# 10bit-adc-and-dac-v2.net
KiCad netlist of a schematic drawn in EAGLE
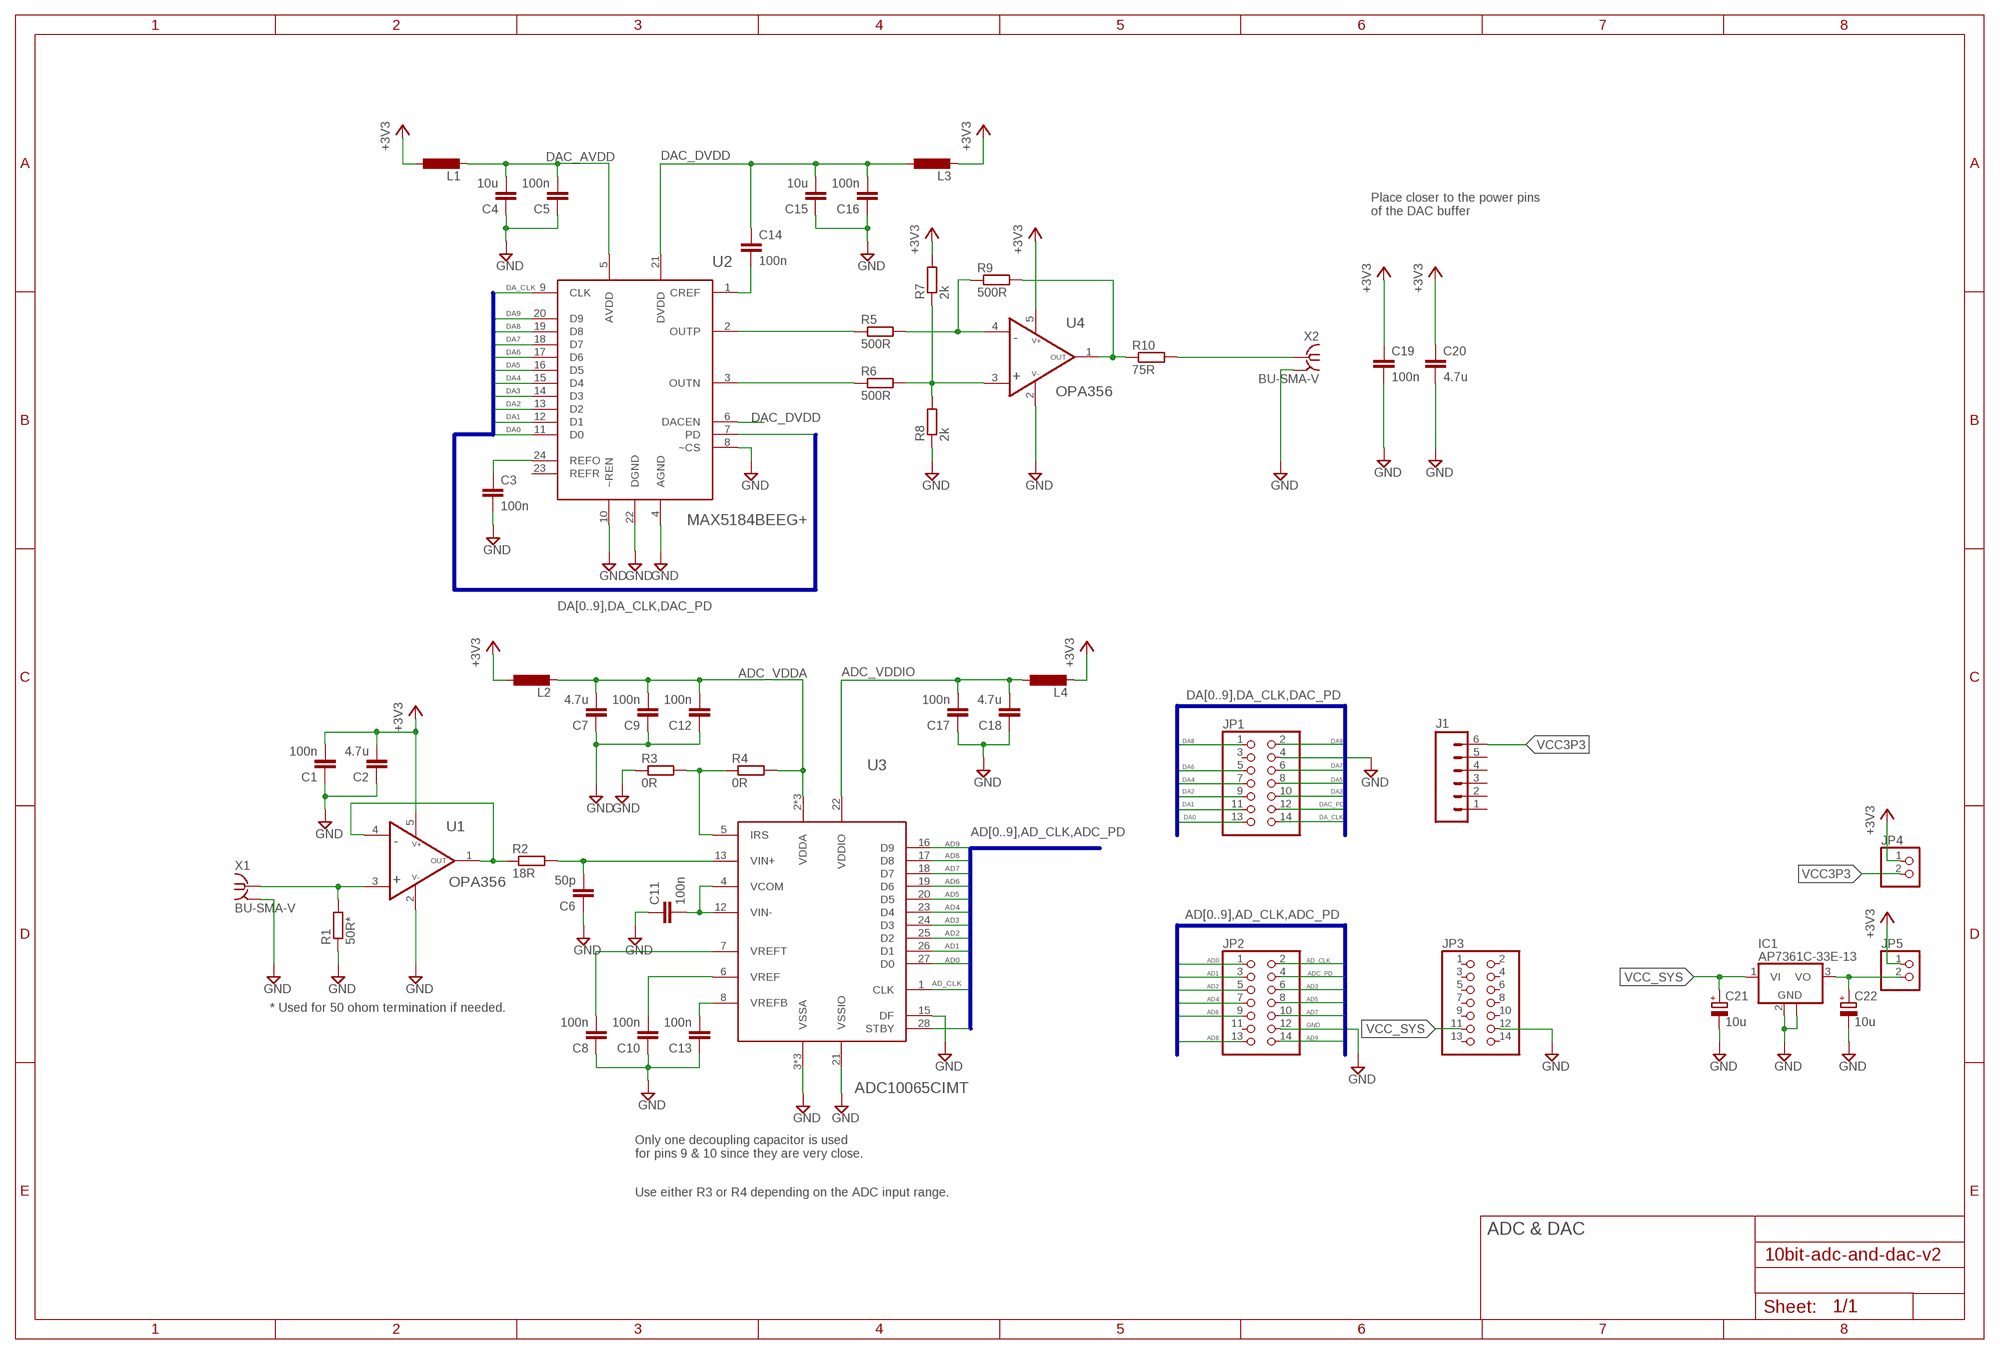
[diagram p0: schematic, sheet 1]

(export (version "E")
  (design (tool "Eeschema 10.0.6"))
  (components
    (comp (ref "C1")
      (value "100n")
      (footprint "eagle-import:C0805")
      (libsource (lib "eagle-import") (part "C-EUC0805"))
    )
    (comp (ref "C2")
      (value "4.7u")
      (footprint "eagle-import:C0805")
      (libsource (lib "eagle-import") (part "C-EUC0805"))
    )
    (comp (ref "C3")
      (value "100n")
      (footprint "eagle-import:C0805")
      (libsource (lib "eagle-import") (part "C-EUC0805"))
    )
    (comp (ref "C4")
      (value "10u")
      (footprint "eagle-import:C0805")
      (libsource (lib "eagle-import") (part "C-EUC0805"))
    )
    (comp (ref "C5")
      (value "100n")
      (footprint "eagle-import:C0805")
      (libsource (lib "eagle-import") (part "C-EUC0805"))
    )
    (comp (ref "C6")
      (value "50p")
      (footprint "eagle-import:C0805")
      (libsource (lib "eagle-import") (part "C-EUC0805"))
    )
    (comp (ref "C7")
      (value "4.7u")
      (footprint "eagle-import:C0805")
      (libsource (lib "eagle-import") (part "C-EUC0805"))
    )
    (comp (ref "C8")
      (value "100n")
      (footprint "eagle-import:C0805")
      (libsource (lib "eagle-import") (part "C-EUC0805"))
    )
    (comp (ref "C9")
      (value "100n")
      (footprint "eagle-import:C0805")
      (libsource (lib "eagle-import") (part "C-EUC0805"))
    )
    (comp (ref "C10")
      (value "100n")
      (footprint "eagle-import:C0805")
      (libsource (lib "eagle-import") (part "C-EUC0805"))
    )
    (comp (ref "C11")
      (value "100n")
      (footprint "eagle-import:C0805")
      (libsource (lib "eagle-import") (part "C-EUC0805"))
    )
    (comp (ref "C12")
      (value "100n")
      (footprint "eagle-import:C0805")
      (libsource (lib "eagle-import") (part "C-EUC0805"))
    )
    (comp (ref "C13")
      (value "100n")
      (footprint "eagle-import:C0805")
      (libsource (lib "eagle-import") (part "C-EUC0805"))
    )
    (comp (ref "C14")
      (value "100n")
      (footprint "eagle-import:C0805")
      (libsource (lib "eagle-import") (part "C-EUC0805"))
    )
    (comp (ref "C15")
      (value "10u")
      (footprint "eagle-import:C0805")
      (libsource (lib "eagle-import") (part "C-EUC0805"))
    )
    (comp (ref "C16")
      (value "100n")
      (footprint "eagle-import:C0805")
      (libsource (lib "eagle-import") (part "C-EUC0805"))
    )
    (comp (ref "C17")
      (value "100n")
      (footprint "eagle-import:C0805")
      (libsource (lib "eagle-import") (part "C-EUC0805"))
    )
    (comp (ref "C18")
      (value "4.7u")
      (footprint "eagle-import:C0805")
      (libsource (lib "eagle-import") (part "C-EUC0805"))
    )
    (comp (ref "C19")
      (value "100n")
      (footprint "eagle-import:C0805")
      (libsource (lib "eagle-import") (part "C-EUC0805"))
    )
    (comp (ref "C20")
      (value "4.7u")
      (footprint "eagle-import:C0805")
      (libsource (lib "eagle-import") (part "C-EUC0805"))
    )
    (comp (ref "C21")
      (value "10u")
      (footprint "eagle-import:CT3528")
      (libsource (lib "eagle-import") (part "CPOL-EUCT3528"))
    )
    (comp (ref "C22")
      (value "10u")
      (footprint "eagle-import:CT3528")
      (libsource (lib "eagle-import") (part "CPOL-EUCT3528"))
    )
    (comp (ref "IC1")
      (value "AP7361C-33E-13")
      (footprint "eagle-import:SOT223")
      (fields (field (name "MF") "Diodes Incorporated"))
      (libsource (lib "eagle-import") (part "UA78MDCY33"))
    )
    (comp (ref "J1")
      (value "M06SILK_FEMALE_PTH")
      (footprint "eagle-import:1X06")
      (libsource (lib "eagle-import") (part "M06SILK_FEMALE_PTH"))
    )
    (comp (ref "JP1")
      (value "PINHD-2X7")
      (footprint "eagle-import:2X07")
      (libsource (lib "eagle-import") (part "PINHD-2X7"))
    )
    (comp (ref "JP2")
      (value "PINHD-2X7")
      (footprint "eagle-import:2X07")
      (libsource (lib "eagle-import") (part "PINHD-2X7"))
    )
    (comp (ref "JP3")
      (value "PINHD-2X7")
      (footprint "eagle-import:2X07")
      (libsource (lib "eagle-import") (part "PINHD-2X7"))
    )
    (comp (ref "JP4")
      (value "PINHD-1X2")
      (footprint "eagle-import:1X02")
      (libsource (lib "eagle-import") (part "PINHD-1X2"))
    )
    (comp (ref "JP5")
      (value "PINHD-1X2")
      (footprint "eagle-import:1X02")
      (libsource (lib "eagle-import") (part "PINHD-1X2"))
    )
    (comp (ref "L1")
      (value "L-EUL2012C")
      (footprint "eagle-import:L2012C")
      (fields (field (name "MPN") "CIM21J252NE"))
      (libsource (lib "eagle-import") (part "L-EUL2012C"))
    )
    (comp (ref "L2")
      (value "L-EUL2012C")
      (footprint "eagle-import:L2012C")
      (fields (field (name "MPN") "CIM21J252NE"))
      (libsource (lib "eagle-import") (part "L-EUL2012C"))
    )
    (comp (ref "L3")
      (value "L-EUL2012C")
      (footprint "eagle-import:L2012C")
      (fields (field (name "MPN") "CIM21J252NE"))
      (libsource (lib "eagle-import") (part "L-EUL2012C"))
    )
    (comp (ref "L4")
      (value "L-EUL2012C")
      (footprint "eagle-import:L2012C")
      (fields (field (name "MPN") "CIM21J252NE"))
      (libsource (lib "eagle-import") (part "L-EUL2012C"))
    )
    (comp (ref "R1")
      (value "50R*")
      (footprint "eagle-import:R0805")
      (libsource (lib "eagle-import") (part "R-EU_R0805"))
    )
    (comp (ref "R2")
      (value "18R")
      (footprint "eagle-import:R0805")
      (libsource (lib "eagle-import") (part "R-EU_R0805"))
    )
    (comp (ref "R3")
      (value "0R")
      (footprint "eagle-import:R0805")
      (libsource (lib "eagle-import") (part "R-EU_R0805"))
    )
    (comp (ref "R4")
      (value "0R")
      (footprint "eagle-import:R0805")
      (libsource (lib "eagle-import") (part "R-EU_R0805"))
    )
    (comp (ref "R5")
      (value "500R")
      (footprint "eagle-import:R0805")
      (libsource (lib "eagle-import") (part "R-EU_R0805"))
    )
    (comp (ref "R6")
      (value "500R")
      (footprint "eagle-import:R0805")
      (libsource (lib "eagle-import") (part "R-EU_R0805"))
    )
    (comp (ref "R7")
      (value "2k")
      (footprint "eagle-import:R0805")
      (libsource (lib "eagle-import") (part "R-EU_R0805"))
    )
    (comp (ref "R8")
      (value "2k")
      (footprint "eagle-import:R0805")
      (libsource (lib "eagle-import") (part "R-EU_R0805"))
    )
    (comp (ref "R9")
      (value "500R")
      (footprint "eagle-import:R0805")
      (libsource (lib "eagle-import") (part "R-EU_R0805"))
    )
    (comp (ref "R10")
      (value "75R")
      (footprint "eagle-import:R0805")
      (libsource (lib "eagle-import") (part "R-EU_R0805"))
    )
    (comp (ref "U1")
      (value "OPA356")
      (footprint "eagle-import:SOT23-5L")
      (fields (field (name "MF") "TI") (field (name "MPN") "OPA356AIDBVR"))
      (libsource (lib "eagle-import") (part "OPA356"))
    )
    (comp (ref "U2")
      (value "MAX5184BEEG+")
      (footprint "eagle-import:SOP63P600X175-24N")
      (fields (field (name "MF") "MAXIM"))
      (libsource (lib "eagle-import") (part "MAX5184BEEG+"))
    )
    (comp (ref "U3")
      (value "ADC10065CIMT")
      (footprint "eagle-import:TSSOP28")
      (fields (field (name "MF") "TI") (field (name "MPN") "ADC10065CIMTX/NOPB"))
      (libsource (lib "eagle-import") (part "ADC10065CIMT"))
    )
    (comp (ref "U4")
      (value "OPA356")
      (footprint "eagle-import:SOT23-5L")
      (fields (field (name "MF") "TI") (field (name "MPN") "OPA356AIDBVR"))
      (libsource (lib "eagle-import") (part "OPA356"))
    )
    (comp (ref "X1")
      (value "BU-SMA-V")
      (footprint "eagle-import:BU-SMA-V")
      (fields (field (name "MF") "TE Connectivity") (field (name "MPN") "5-1814832-1"))
      (libsource (lib "eagle-import") (part "BU-SMA-V"))
    )
    (comp (ref "X2")
      (value "BU-SMA-V")
      (footprint "eagle-import:BU-SMA-V")
      (fields (field (name "MF") "TE Connectivity") (field (name "MPN") "5-1814832-1"))
      (libsource (lib "eagle-import") (part "BU-SMA-V"))
    )
  )
  (nets
    (net (code "1") (name "+3V3") (class "Default")
      (node (ref "C1") (pin "2") (pinfunction "2_2") (pintype "passive"))
      (node (ref "C19") (pin "1") (pinfunction "1_1") (pintype "passive"))
      (node (ref "C2") (pin "2") (pinfunction "2_2") (pintype "passive"))
      (node (ref "C20") (pin "1") (pinfunction "1_1") (pintype "passive"))
      (node (ref "JP4") (pin "1") (pinfunction "1_1") (pintype "passive"))
      (node (ref "JP5") (pin "1") (pinfunction "1_1") (pintype "passive"))
      (node (ref "L1") (pin "1") (pinfunction "1_1") (pintype "passive"))
      (node (ref "L2") (pin "1") (pinfunction "1_1") (pintype "passive"))
      (node (ref "L3") (pin "2") (pinfunction "2_2") (pintype "passive"))
      (node (ref "L4") (pin "2") (pinfunction "2_2") (pintype "passive"))
      (node (ref "R7") (pin "2") (pinfunction "2_2") (pintype "passive"))
      (node (ref "U1") (pin "5") (pinfunction "V+_5") (pintype "power_in"))
      (node (ref "U4") (pin "5") (pinfunction "V+_5") (pintype "power_in"))
    )
    (net (code "2") (name "/AD0") (class "Default")
      (node (ref "JP2") (pin "1") (pinfunction "1_1") (pintype "passive"))
      (node (ref "U3") (pin "27") (pinfunction "D0_27") (pintype "bidirectional"))
    )
    (net (code "3") (name "/AD1") (class "Default")
      (node (ref "JP2") (pin "3") (pinfunction "3_3") (pintype "passive"))
      (node (ref "U3") (pin "26") (pinfunction "D1_26") (pintype "bidirectional"))
    )
    (net (code "4") (name "/AD2") (class "Default")
      (node (ref "JP2") (pin "5") (pinfunction "5_5") (pintype "passive"))
      (node (ref "U3") (pin "25") (pinfunction "D2_25") (pintype "bidirectional"))
    )
    (net (code "5") (name "/AD3") (class "Default")
      (node (ref "JP2") (pin "6") (pinfunction "6_6") (pintype "passive"))
      (node (ref "U3") (pin "24") (pinfunction "D3_24") (pintype "bidirectional"))
    )
    (net (code "6") (name "/AD4") (class "Default")
      (node (ref "JP2") (pin "7") (pinfunction "7_7") (pintype "passive"))
      (node (ref "U3") (pin "23") (pinfunction "D4_23") (pintype "bidirectional"))
    )
    (net (code "7") (name "/AD5") (class "Default")
      (node (ref "JP2") (pin "8") (pinfunction "8_8") (pintype "passive"))
      (node (ref "U3") (pin "20") (pinfunction "D5_20") (pintype "bidirectional"))
    )
    (net (code "8") (name "/AD6") (class "Default")
      (node (ref "JP2") (pin "9") (pinfunction "9_9") (pintype "passive"))
      (node (ref "U3") (pin "19") (pinfunction "D6_19") (pintype "bidirectional"))
    )
    (net (code "9") (name "/AD7") (class "Default")
      (node (ref "JP2") (pin "10") (pinfunction "10_10") (pintype "passive"))
      (node (ref "U3") (pin "18") (pinfunction "D7_18") (pintype "bidirectional"))
    )
    (net (code "10") (name "/AD8") (class "Default")
      (node (ref "JP2") (pin "13") (pinfunction "13_13") (pintype "passive"))
      (node (ref "U3") (pin "17") (pinfunction "D8_17") (pintype "bidirectional"))
    )
    (net (code "11") (name "/AD9") (class "Default")
      (node (ref "JP2") (pin "14") (pinfunction "14_14") (pintype "passive"))
      (node (ref "U3") (pin "16") (pinfunction "D9_16") (pintype "bidirectional"))
    )
    (net (code "12") (name "/ADC_PD") (class "Default")
      (node (ref "JP2") (pin "4") (pinfunction "4_4") (pintype "passive"))
      (node (ref "U3") (pin "28") (pinfunction "STBY_28") (pintype "bidirectional"))
    )
    (net (code "13") (name "/ADC_VDDA") (class "Default")
      (node (ref "C12") (pin "2") (pinfunction "2_2") (pintype "passive"))
      (node (ref "C7") (pin "2") (pinfunction "2_2") (pintype "passive"))
      (node (ref "C9") (pin "2") (pinfunction "2_2") (pintype "passive"))
      (node (ref "L2") (pin "2") (pinfunction "2_2") (pintype "passive"))
      (node (ref "R4") (pin "2") (pinfunction "2_2") (pintype "passive"))
      (node (ref "U3") (pin "10") (pinfunction "VDDA_10") (pintype "bidirectional"))
      (node (ref "U3") (pin "2") (pinfunction "VDDA_2") (pintype "bidirectional"))
      (node (ref "U3") (pin "9") (pinfunction "VDDA_9") (pintype "bidirectional"))
    )
    (net (code "14") (name "/ADC_VDDIO") (class "Default")
      (node (ref "C17") (pin "2") (pinfunction "2_2") (pintype "passive"))
      (node (ref "C18") (pin "2") (pinfunction "2_2") (pintype "passive"))
      (node (ref "L4") (pin "1") (pinfunction "1_1") (pintype "passive"))
      (node (ref "U3") (pin "22") (pinfunction "VDDIO_22") (pintype "bidirectional"))
    )
    (net (code "15") (name "/AD_CLK") (class "Default")
      (node (ref "JP2") (pin "2") (pinfunction "2_2") (pintype "passive"))
      (node (ref "U3") (pin "1") (pinfunction "CLK_1") (pintype "bidirectional"))
    )
    (net (code "16") (name "/DA0") (class "Default")
      (node (ref "JP1") (pin "13") (pinfunction "13_13") (pintype "passive"))
      (node (ref "U2") (pin "11") (pinfunction "D0_11") (pintype "bidirectional"))
    )
    (net (code "17") (name "/DA1") (class "Default")
      (node (ref "JP1") (pin "11") (pinfunction "11_11") (pintype "passive"))
      (node (ref "U2") (pin "12") (pinfunction "D1_12") (pintype "bidirectional"))
    )
    (net (code "18") (name "/DA2") (class "Default")
      (node (ref "JP1") (pin "9") (pinfunction "9_9") (pintype "passive"))
      (node (ref "U2") (pin "13") (pinfunction "D2_13") (pintype "bidirectional"))
    )
    (net (code "19") (name "/DA3") (class "Default")
      (node (ref "JP1") (pin "10") (pinfunction "10_10") (pintype "passive"))
      (node (ref "U2") (pin "14") (pinfunction "D3_14") (pintype "bidirectional"))
    )
    (net (code "20") (name "/DA4") (class "Default")
      (node (ref "JP1") (pin "7") (pinfunction "7_7") (pintype "passive"))
      (node (ref "U2") (pin "15") (pinfunction "D4_15") (pintype "bidirectional"))
    )
    (net (code "21") (name "/DA5") (class "Default")
      (node (ref "JP1") (pin "8") (pinfunction "8_8") (pintype "passive"))
      (node (ref "U2") (pin "16") (pinfunction "D5_16") (pintype "bidirectional"))
    )
    (net (code "22") (name "/DA6") (class "Default")
      (node (ref "JP1") (pin "5") (pinfunction "5_5") (pintype "passive"))
      (node (ref "U2") (pin "17") (pinfunction "D6_17") (pintype "bidirectional"))
    )
    (net (code "23") (name "/DA7") (class "Default")
      (node (ref "JP1") (pin "6") (pinfunction "6_6") (pintype "passive"))
      (node (ref "U2") (pin "18") (pinfunction "D7_18") (pintype "bidirectional"))
    )
    (net (code "24") (name "/DA8") (class "Default")
      (node (ref "JP1") (pin "1") (pinfunction "1_1") (pintype "passive"))
      (node (ref "U2") (pin "19") (pinfunction "D8_19") (pintype "bidirectional"))
    )
    (net (code "25") (name "/DA9") (class "Default")
      (node (ref "JP1") (pin "2") (pinfunction "2_2") (pintype "passive"))
      (node (ref "U2") (pin "20") (pinfunction "D9_20") (pintype "bidirectional"))
    )
    (net (code "26") (name "/DAC_AVDD") (class "Default")
      (node (ref "C4") (pin "2") (pinfunction "2_2") (pintype "passive"))
      (node (ref "C5") (pin "2") (pinfunction "2_2") (pintype "passive"))
      (node (ref "L1") (pin "2") (pinfunction "2_2") (pintype "passive"))
      (node (ref "U2") (pin "5") (pinfunction "AVDD_5") (pintype "bidirectional"))
    )
    (net (code "27") (name "/DAC_DVDD") (class "Default")
      (node (ref "C14") (pin "1") (pinfunction "1_1") (pintype "passive"))
      (node (ref "C15") (pin "2") (pinfunction "2_2") (pintype "passive"))
      (node (ref "C16") (pin "2") (pinfunction "2_2") (pintype "passive"))
      (node (ref "L3") (pin "1") (pinfunction "1_1") (pintype "passive"))
      (node (ref "U2") (pin "21") (pinfunction "DVDD_21") (pintype "bidirectional"))
      (node (ref "U2") (pin "6") (pinfunction "DACEN_6") (pintype "bidirectional"))
    )
    (net (code "28") (name "/DAC_PD") (class "Default")
      (node (ref "JP1") (pin "12") (pinfunction "12_12") (pintype "passive"))
      (node (ref "U2") (pin "7") (pinfunction "PD_7") (pintype "bidirectional"))
    )
    (net (code "29") (name "/DA_CLK") (class "Default")
      (node (ref "JP1") (pin "14") (pinfunction "14_14") (pintype "passive"))
      (node (ref "U2") (pin "9") (pinfunction "CLK_9") (pintype "bidirectional"))
    )
    (net (code "32") (name "GND") (class "Default")
      (node (ref "C1") (pin "1") (pinfunction "1_1") (pintype "passive"))
      (node (ref "C10") (pin "1") (pinfunction "1_1") (pintype "passive"))
      (node (ref "C11") (pin "1") (pinfunction "1_1") (pintype "passive"))
      (node (ref "C12") (pin "1") (pinfunction "1_1") (pintype "passive"))
      (node (ref "C13") (pin "1") (pinfunction "1_1") (pintype "passive"))
      (node (ref "C15") (pin "1") (pinfunction "1_1") (pintype "passive"))
      (node (ref "C16") (pin "1") (pinfunction "1_1") (pintype "passive"))
      (node (ref "C17") (pin "1") (pinfunction "1_1") (pintype "passive"))
      (node (ref "C18") (pin "1") (pinfunction "1_1") (pintype "passive"))
      (node (ref "C19") (pin "2") (pinfunction "2_2") (pintype "passive"))
      (node (ref "C2") (pin "1") (pinfunction "1_1") (pintype "passive"))
      (node (ref "C20") (pin "2") (pinfunction "2_2") (pintype "passive"))
      (node (ref "C21") (pin "-") (pinfunction "-_-") (pintype "passive"))
      (node (ref "C22") (pin "-") (pinfunction "-_-") (pintype "passive"))
      (node (ref "C3") (pin "2") (pinfunction "2_2") (pintype "passive"))
      (node (ref "C4") (pin "1") (pinfunction "1_1") (pintype "passive"))
      (node (ref "C5") (pin "1") (pinfunction "1_1") (pintype "passive"))
      (node (ref "C6") (pin "1") (pinfunction "1_1") (pintype "passive"))
      (node (ref "C7") (pin "1") (pinfunction "1_1") (pintype "passive"))
      (node (ref "C8") (pin "1") (pinfunction "1_1") (pintype "passive"))
      (node (ref "C9") (pin "1") (pinfunction "1_1") (pintype "passive"))
      (node (ref "IC1") (pin "2") (pinfunction "GND_2") (pintype "passive"))
      (node (ref "IC1") (pin "4") (pinfunction "GND_4") (pintype "passive"))
      (node (ref "JP1") (pin "4") (pinfunction "4_4") (pintype "passive"))
      (node (ref "JP2") (pin "12") (pinfunction "12_12") (pintype "passive"))
      (node (ref "JP3") (pin "12") (pinfunction "12_12") (pintype "passive"))
      (node (ref "R1") (pin "1") (pinfunction "1_1") (pintype "passive"))
      (node (ref "R3") (pin "1") (pinfunction "1_1") (pintype "passive"))
      (node (ref "R8") (pin "1") (pinfunction "1_1") (pintype "passive"))
      (node (ref "U1") (pin "2") (pinfunction "V-_2") (pintype "power_in"))
      (node (ref "U2") (pin "10") (pinfunction "~{REN}_10") (pintype "bidirectional"))
      (node (ref "U2") (pin "22") (pinfunction "DGND_22") (pintype "bidirectional"))
      (node (ref "U2") (pin "4") (pinfunction "AGND_4") (pintype "bidirectional"))
      (node (ref "U2") (pin "8") (pinfunction "~{CS}_8") (pintype "bidirectional"))
      (node (ref "U3") (pin "11") (pinfunction "VSSA_11") (pintype "bidirectional"))
      (node (ref "U3") (pin "14") (pinfunction "VSSA_14") (pintype "bidirectional"))
      (node (ref "U3") (pin "15") (pinfunction "DF_15") (pintype "bidirectional"))
      (node (ref "U3") (pin "21") (pinfunction "VSSIO_21") (pintype "bidirectional"))
      (node (ref "U3") (pin "3") (pinfunction "VSSA_3") (pintype "bidirectional"))
      (node (ref "U4") (pin "2") (pinfunction "V-_2") (pintype "power_in"))
      (node (ref "X1") (pin "2") (pinfunction "2_2") (pintype "passive"))
      (node (ref "X1") (pin "3") (pinfunction "2_3") (pintype "passive"))
      (node (ref "X1") (pin "4") (pinfunction "2_4") (pintype "passive"))
      (node (ref "X1") (pin "5") (pinfunction "2_5") (pintype "passive"))
      (node (ref "X2") (pin "2") (pinfunction "2_2") (pintype "passive"))
      (node (ref "X2") (pin "3") (pinfunction "2_3") (pintype "passive"))
      (node (ref "X2") (pin "4") (pinfunction "2_4") (pintype "passive"))
      (node (ref "X2") (pin "5") (pinfunction "2_5") (pintype "passive"))
    )
    (net (code "33") (name "Net-(IC1-VO)") (class "Default")
      (node (ref "C22") (pin "+") (pinfunction "+_+") (pintype "passive"))
      (node (ref "IC1") (pin "3") (pinfunction "VO_3") (pintype "passive"))
      (node (ref "JP5") (pin "2") (pinfunction "2_2") (pintype "passive"))
    )
    (net (code "34") (name "Net-(R10-Pad2)") (class "Default")
      (node (ref "R10") (pin "2") (pinfunction "2_2") (pintype "passive"))
      (node (ref "X2") (pin "1") (pinfunction "1_1") (pintype "passive"))
    )
    (net (code "35") (name "Net-(U1-IN+)") (class "Default")
      (node (ref "R1") (pin "2") (pinfunction "2_2") (pintype "passive"))
      (node (ref "U1") (pin "3") (pinfunction "IN+_3") (pintype "input"))
      (node (ref "X1") (pin "1") (pinfunction "1_1") (pintype "passive"))
    )
    (net (code "36") (name "Net-(U1-IN-)") (class "Default")
      (node (ref "R2") (pin "1") (pinfunction "1_1") (pintype "passive"))
      (node (ref "U1") (pin "1") (pinfunction "OUT_1") (pintype "output"))
      (node (ref "U1") (pin "4") (pinfunction "IN-_4") (pintype "input"))
    )
    (net (code "37") (name "Net-(U2-CREF)") (class "Default")
      (node (ref "C14") (pin "2") (pinfunction "2_2") (pintype "passive"))
      (node (ref "U2") (pin "1") (pinfunction "CREF_1") (pintype "bidirectional"))
    )
    (net (code "38") (name "Net-(U2-OUTN)") (class "Default")
      (node (ref "R6") (pin "1") (pinfunction "1_1") (pintype "passive"))
      (node (ref "U2") (pin "3") (pinfunction "OUTN_3") (pintype "bidirectional"))
    )
    (net (code "39") (name "Net-(U2-OUTP)") (class "Default")
      (node (ref "R5") (pin "1") (pinfunction "1_1") (pintype "passive"))
      (node (ref "U2") (pin "2") (pinfunction "OUTP_2") (pintype "bidirectional"))
    )
    (net (code "40") (name "Net-(U2-REFO)") (class "Default")
      (node (ref "C3") (pin "1") (pinfunction "1_1") (pintype "passive"))
      (node (ref "U2") (pin "24") (pinfunction "REFO_24") (pintype "bidirectional"))
    )
    (net (code "41") (name "Net-(U3-IRS)") (class "Default")
      (node (ref "R3") (pin "2") (pinfunction "2_2") (pintype "passive"))
      (node (ref "R4") (pin "1") (pinfunction "1_1") (pintype "passive"))
      (node (ref "U3") (pin "5") (pinfunction "IRS_5") (pintype "bidirectional"))
    )
    (net (code "42") (name "Net-(U3-VCOM)") (class "Default")
      (node (ref "C11") (pin "2") (pinfunction "2_2") (pintype "passive"))
      (node (ref "U3") (pin "12") (pinfunction "VIN-_12") (pintype "bidirectional"))
      (node (ref "U3") (pin "4") (pinfunction "VCOM_4") (pintype "bidirectional"))
    )
    (net (code "43") (name "Net-(U3-VIN+)") (class "Default")
      (node (ref "C6") (pin "2") (pinfunction "2_2") (pintype "passive"))
      (node (ref "R2") (pin "2") (pinfunction "2_2") (pintype "passive"))
      (node (ref "U3") (pin "13") (pinfunction "VIN+_13") (pintype "bidirectional"))
    )
    (net (code "44") (name "Net-(U3-VREF)") (class "Default")
      (node (ref "C10") (pin "2") (pinfunction "2_2") (pintype "passive"))
      (node (ref "U3") (pin "6") (pinfunction "VREF_6") (pintype "bidirectional"))
    )
    (net (code "45") (name "Net-(U3-VREFB)") (class "Default")
      (node (ref "C13") (pin "2") (pinfunction "2_2") (pintype "passive"))
      (node (ref "U3") (pin "8") (pinfunction "VREFB_8") (pintype "bidirectional"))
    )
    (net (code "46") (name "Net-(U3-VREFT)") (class "Default")
      (node (ref "C8") (pin "2") (pinfunction "2_2") (pintype "passive"))
      (node (ref "U3") (pin "7") (pinfunction "VREFT_7") (pintype "bidirectional"))
    )
    (net (code "47") (name "Net-(U4-IN+)") (class "Default")
      (node (ref "R6") (pin "2") (pinfunction "2_2") (pintype "passive"))
      (node (ref "R7") (pin "1") (pinfunction "1_1") (pintype "passive"))
      (node (ref "R8") (pin "2") (pinfunction "2_2") (pintype "passive"))
      (node (ref "U4") (pin "3") (pinfunction "IN+_3") (pintype "input"))
    )
    (net (code "48") (name "Net-(U4-IN-)") (class "Default")
      (node (ref "R5") (pin "2") (pinfunction "2_2") (pintype "passive"))
      (node (ref "R9") (pin "1") (pinfunction "1_1") (pintype "passive"))
      (node (ref "U4") (pin "4") (pinfunction "IN-_4") (pintype "input"))
    )
    (net (code "49") (name "Net-(U4-OUT)") (class "Default")
      (node (ref "R10") (pin "1") (pinfunction "1_1") (pintype "passive"))
      (node (ref "R9") (pin "2") (pinfunction "2_2") (pintype "passive"))
      (node (ref "U4") (pin "1") (pinfunction "OUT_1") (pintype "output"))
    )
    (net (code "50") (name "VCC3P3") (class "Default")
      (node (ref "J1") (pin "6") (pinfunction "6_6") (pintype "passive"))
      (node (ref "JP4") (pin "2") (pinfunction "2_2") (pintype "passive"))
    )
    (net (code "51") (name "VCC_SYS") (class "Default")
      (node (ref "C21") (pin "+") (pinfunction "+_+") (pintype "passive"))
      (node (ref "IC1") (pin "1") (pinfunction "VI_1") (pintype "input"))
      (node (ref "JP3") (pin "11") (pinfunction "11_11") (pintype "passive"))
    )
    (net (code "52") (name "unconnected-(J1-Pad1)") (class "Default")
      (node (ref "J1") (pin "1") (pinfunction "1_1") (pintype "passive"))
    )
    (net (code "53") (name "unconnected-(J1-Pad2)") (class "Default")
      (node (ref "J1") (pin "2") (pinfunction "2_2") (pintype "passive"))
    )
    (net (code "54") (name "unconnected-(J1-Pad3)") (class "Default")
      (node (ref "J1") (pin "3") (pinfunction "3_3") (pintype "passive"))
    )
    (net (code "55") (name "unconnected-(J1-Pad4)") (class "Default")
      (node (ref "J1") (pin "4") (pinfunction "4_4") (pintype "passive"))
    )
    (net (code "56") (name "unconnected-(J1-Pad5)") (class "Default")
      (node (ref "J1") (pin "5") (pinfunction "5_5") (pintype "passive"))
    )
    (net (code "57") (name "unconnected-(JP1-Pad3)") (class "Default")
      (node (ref "JP1") (pin "3") (pinfunction "3_3") (pintype "passive"))
    )
    (net (code "58") (name "unconnected-(JP2-Pad11)") (class "Default")
      (node (ref "JP2") (pin "11") (pinfunction "11_11") (pintype "passive"))
    )
    (net (code "59") (name "unconnected-(JP3-Pad1)") (class "Default")
      (node (ref "JP3") (pin "1") (pinfunction "1_1") (pintype "passive"))
    )
    (net (code "60") (name "unconnected-(JP3-Pad2)") (class "Default")
      (node (ref "JP3") (pin "2") (pinfunction "2_2") (pintype "passive"))
    )
    (net (code "61") (name "unconnected-(JP3-Pad3)") (class "Default")
      (node (ref "JP3") (pin "3") (pinfunction "3_3") (pintype "passive"))
    )
    (net (code "62") (name "unconnected-(JP3-Pad4)") (class "Default")
      (node (ref "JP3") (pin "4") (pinfunction "4_4") (pintype "passive"))
    )
    (net (code "63") (name "unconnected-(JP3-Pad5)") (class "Default")
      (node (ref "JP3") (pin "5") (pinfunction "5_5") (pintype "passive"))
    )
    (net (code "64") (name "unconnected-(JP3-Pad6)") (class "Default")
      (node (ref "JP3") (pin "6") (pinfunction "6_6") (pintype "passive"))
    )
    (net (code "65") (name "unconnected-(JP3-Pad7)") (class "Default")
      (node (ref "JP3") (pin "7") (pinfunction "7_7") (pintype "passive"))
    )
    (net (code "66") (name "unconnected-(JP3-Pad8)") (class "Default")
      (node (ref "JP3") (pin "8") (pinfunction "8_8") (pintype "passive"))
    )
    (net (code "67") (name "unconnected-(JP3-Pad9)") (class "Default")
      (node (ref "JP3") (pin "9") (pinfunction "9_9") (pintype "passive"))
    )
    (net (code "68") (name "unconnected-(JP3-Pad10)") (class "Default")
      (node (ref "JP3") (pin "10") (pinfunction "10_10") (pintype "passive"))
    )
    (net (code "69") (name "unconnected-(JP3-Pad13)") (class "Default")
      (node (ref "JP3") (pin "13") (pinfunction "13_13") (pintype "passive"))
    )
    (net (code "70") (name "unconnected-(JP3-Pad14)") (class "Default")
      (node (ref "JP3") (pin "14") (pinfunction "14_14") (pintype "passive"))
    )
    (net (code "71") (name "unconnected-(U2-REFR-Pad23)") (class "Default")
      (node (ref "U2") (pin "23") (pinfunction "REFR_23") (pintype "bidirectional"))
    )
  )
)
